# 06_IN_OUT.net
KiCad netlist of a schematic drawn in Altium Designer
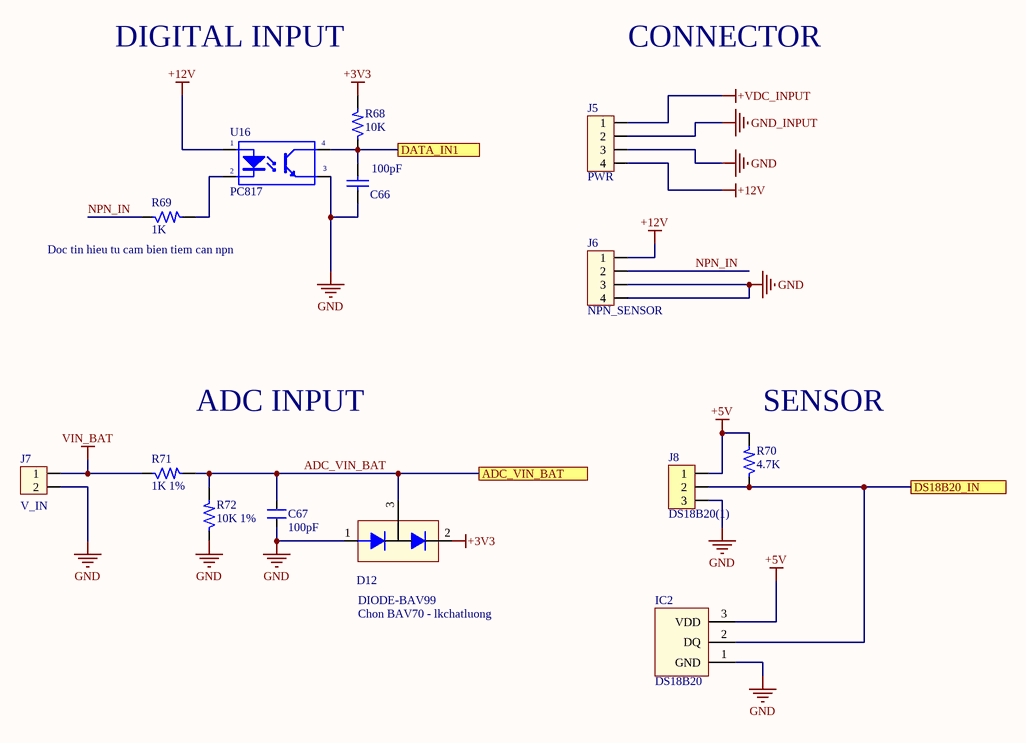
[diagram p0: [06]IN_OUT.SchDoc]

(export (version "E")
  (design (tool "Eeschema 10.0.6"))
  (components
    (comp (ref "C66")
      (value "100pF")
      (footprint "CAP_0805")
      (description "Capacitor")
      (fields (field (name "PUBLISHER") "Altium Limited"))
      (libsource (lib "My Library") (part "CapSMD"))
    )
    (comp (ref "C67")
      (value "100pF")
      (footprint "CAP_0805")
      (description "Cap SMD")
      (libsource (lib "khapham") (part "CM"))
    )
    (comp (ref "D12")
      (value "DIODE-BAV99")
      (footprint "SOT23")
      (description "ZENER, SOT23,")
      (fields
        (field (name "MANUFACTURER") "ON Semiconductor / Fairchild")
        (field (name "MANUFACTURER PART NUMBER") "BAV99")
        (field (name ".CREATOR") "LeKhaLinh")
        (field (name ".CHECKPCB") "LeKhaLinh")
        (field (name ".CHECKSCH") "LeKhaLinh")
      )
      (libsource (lib "GPS_Traking_V1_1") (part "DIODE-BAV99"))
    )
    (comp (ref "IC2")
      (value "DS18B20")
      (footprint "TO92")
      (description "High Precision  1-Wire® Digital Thermometer")
      (libsource (lib "My Library") (part "DS18S20"))
    )
    (comp (ref "J5")
      (value "PWR")
      (footprint "Hed4V_3.96")
      (description "Header 4 (Green)")
      (libsource (lib "GPS_Traking_V1_1") (part "Hed4"))
    )
    (comp (ref "J6")
      (value "NPN_SENSOR")
      (footprint "CON_2.54mm_4")
      (description "Connector 4")
      (libsource (lib "GPS_Traking_V1_1") (part "Con4"))
    )
    (comp (ref "J7")
      (value "V_IN")
      (footprint "CON_2.54mm_2")
      (description "Connector 2")
      (libsource (lib "GPS_Traking_V1_1") (part "Con2"))
    )
    (comp (ref "J8")
      (value "DS18B20(1)")
      (footprint "Header3")
      (description "Header IDC, 3 x 1 Pin Vertical 2.54mm Pitch (Non-Boxed, Male)")
      (fields
        (field (name "MANUFACTURER") "Würth Elektronik eiSos GmbH")
        (field (name "PARTNO") "613002143121")
        (field (name "CREATED BY") "Karrer Zheng")
      )
      (libsource (lib "My Library") (part "Header3"))
    )
    (comp (ref "R68")
      (value "10K")
      (footprint "RES-SMD-0805")
      (description "Resistor SMD")
      (libsource (lib "khapham") (part "RM"))
    )
    (comp (ref "R69")
      (value "1K")
      (footprint "RES-SMD-0805")
      (description "Resistor SMD")
      (libsource (lib "khapham") (part "RM"))
    )
    (comp (ref "R70")
      (value "4.7K")
      (footprint "RES-SMD-0805")
      (description "Resistor SMD")
      (libsource (lib "khapham") (part "RM"))
    )
    (comp (ref "R71")
      (value "1K 1%")
      (footprint "RES-SMD-0805")
      (description "Resistor SMD")
      (libsource (lib "khapham") (part "RM"))
    )
    (comp (ref "R72")
      (value "10K 1%")
      (footprint "RES-SMD-0805")
      (description "Resistor SMD")
      (libsource (lib "khapham") (part "RM"))
    )
    (comp (ref "U16")
      (value "PC817")
      (footprint "PC817x1SMD")
      (description "Single Opto")
      (libsource (lib "GPS_Traking_V1_1") (part "PC817"))
    )
  )
  (nets
    (net (code "1") (name "+3V3") (class "Default")
      (node (ref "D12") (pin "2") (pinfunction "2_2") (pintype "passive"))
      (node (ref "R68") (pin "2") (pinfunction "2_2") (pintype "passive"))
    )
    (net (code "2") (name "+5V") (class "Default")
      (node (ref "IC2") (pin "3") (pinfunction "VDD_3") (pintype "passive"))
      (node (ref "J8") (pin "1") (pinfunction "1_1") (pintype "passive"))
      (node (ref "R70") (pin "2") (pinfunction "2_2") (pintype "passive"))
    )
    (net (code "3") (name "+12V") (class "Default")
      (node (ref "J5") (pin "4") (pinfunction "4_4") (pintype "passive"))
      (node (ref "J6") (pin "1") (pinfunction "1_1") (pintype "passive"))
      (node (ref "U16") (pin "1") (pinfunction "A_1") (pintype "passive"))
    )
    (net (code "4") (name "+VDC_INPUT") (class "Default")
      (node (ref "J5") (pin "1") (pinfunction "1_1") (pintype "passive"))
    )
    (net (code "5") (name "/ADC_VIN_BAT") (class "Default")
      (node (ref "C67") (pin "2") (pinfunction "2_2") (pintype "passive"))
      (node (ref "D12") (pin "3") (pinfunction "3_3") (pintype "passive"))
      (node (ref "R71") (pin "2") (pinfunction "2_2") (pintype "passive"))
      (node (ref "R72") (pin "2") (pinfunction "2_2") (pintype "passive"))
    )
    (net (code "6") (name "/DATA_IN1") (class "Default")
      (node (ref "C66") (pin "1") (pinfunction "1_1") (pintype "passive"))
      (node (ref "R68") (pin "1") (pinfunction "1_1") (pintype "passive"))
      (node (ref "U16") (pin "4") (pinfunction "C_4") (pintype "passive"))
    )
    (net (code "7") (name "/DS18B20_IN") (class "Default")
      (node (ref "IC2") (pin "2") (pinfunction "DQ_2") (pintype "passive"))
      (node (ref "J8") (pin "2") (pinfunction "2_2") (pintype "passive"))
      (node (ref "R70") (pin "1") (pinfunction "1_1") (pintype "passive"))
    )
    (net (code "8") (name "/NPN_IN") (class "Default")
      (node (ref "J6") (pin "2") (pinfunction "2_2") (pintype "passive"))
      (node (ref "R69") (pin "1") (pinfunction "1_1") (pintype "passive"))
    )
    (net (code "9") (name "GND") (class "Default")
      (node (ref "C66") (pin "2") (pinfunction "2_2") (pintype "passive"))
      (node (ref "C67") (pin "1") (pinfunction "1_1") (pintype "passive"))
      (node (ref "D12") (pin "1") (pinfunction "1_1") (pintype "passive"))
      (node (ref "IC2") (pin "1") (pinfunction "GND_1") (pintype "passive"))
      (node (ref "J5") (pin "3") (pinfunction "3_3") (pintype "passive"))
      (node (ref "J6") (pin "3") (pinfunction "3_3") (pintype "passive"))
      (node (ref "J6") (pin "4") (pinfunction "4_4") (pintype "passive"))
      (node (ref "J7") (pin "2") (pinfunction "2_2") (pintype "passive"))
      (node (ref "J8") (pin "3") (pinfunction "3_3") (pintype "passive"))
      (node (ref "R72") (pin "1") (pinfunction "1_1") (pintype "passive"))
      (node (ref "U16") (pin "3") (pinfunction "E_3") (pintype "passive"))
    )
    (net (code "10") (name "GND_INPUT") (class "Default")
      (node (ref "J5") (pin "2") (pinfunction "2_2") (pintype "passive"))
    )
    (net (code "11") (name "Net-(U16-K)") (class "Default")
      (node (ref "R69") (pin "2") (pinfunction "2_2") (pintype "passive"))
      (node (ref "U16") (pin "2") (pinfunction "K_2") (pintype "passive"))
    )
    (net (code "12") (name "VIN_BAT") (class "Default")
      (node (ref "J7") (pin "1") (pinfunction "1_1") (pintype "passive"))
      (node (ref "R71") (pin "1") (pinfunction "1_1") (pintype "passive"))
    )
  )
)
